# Transmitter.net
KiCad netlist of a schematic drawn in EAGLE
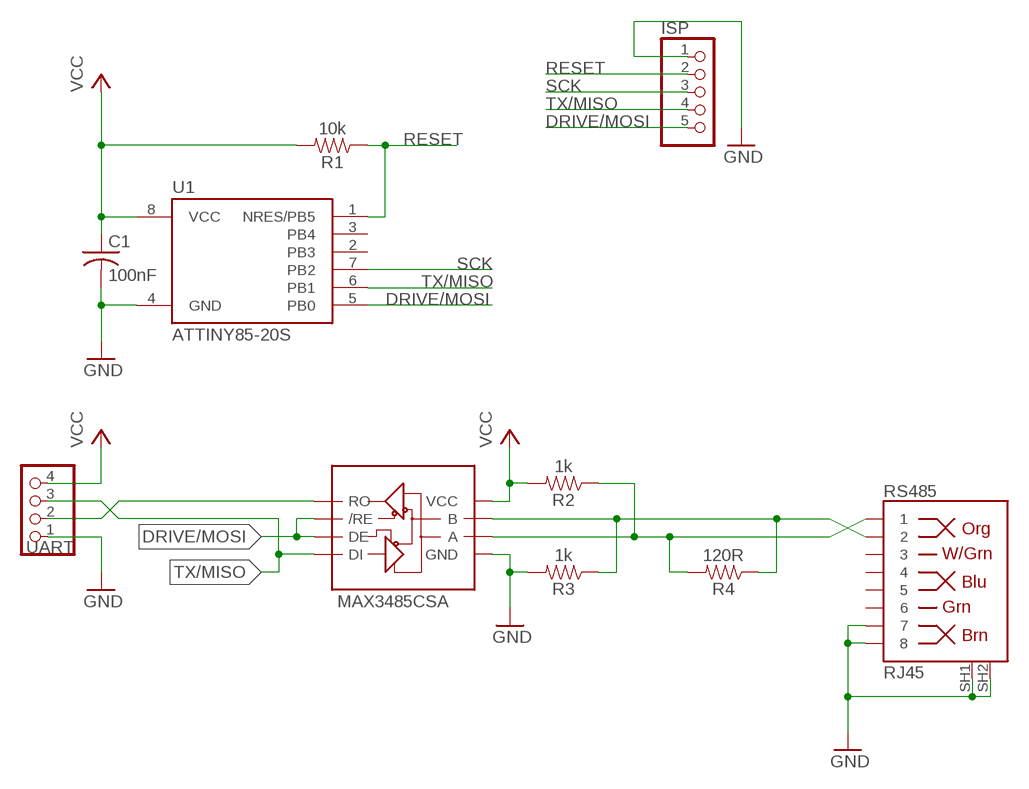
[diagram p0: schematic, sheet 1]

(export (version "E")
  (design (tool "Eeschema 10.0.6"))
  (components
    (comp (ref "C1")
      (value "100nF")
      (footprint "eagle-import:C0603")
      (fields (field (name "MPN") "CC0201KRX5R5BB104"))
      (libsource (lib "eagle-import") (part "C-USC0603"))
    )
    (comp (ref "ISP")
      (value "PINHD-1X5")
      (footprint "eagle-import:1X05")
      (libsource (lib "eagle-import") (part "PINHD-1X5"))
    )
    (comp (ref "R1")
      (value "10k")
      (footprint "eagle-import:0603")
      (libsource (lib "eagle-import") (part "10KOHM-0603-1/10W-1%"))
    )
    (comp (ref "R2")
      (value "1k")
      (footprint "eagle-import:0603")
      (libsource (lib "eagle-import") (part "1KOHM-0603-1/10W-1%"))
    )
    (comp (ref "R3")
      (value "1k")
      (footprint "eagle-import:0603")
      (libsource (lib "eagle-import") (part "1KOHM-0603-1/10W-1%"))
    )
    (comp (ref "R4")
      (value "120R")
      (footprint "eagle-import:0805")
      (libsource (lib "eagle-import") (part "RESISTOR0805"))
    )
    (comp (ref "RS485")
      (value "RJ45")
      (footprint "eagle-import:RJ45-8")
      (libsource (lib "eagle-import") (part "RJ45-8"))
    )
    (comp (ref "U1")
      (value "ATTINY85-20S")
      (footprint "eagle-import:SOIC8_EIAJ_208MIL")
      (libsource (lib "eagle-import") (part "ATTINY85S-20"))
    )
    (comp (ref "U2")
      (value "MAX3485CSA")
      (footprint "eagle-import:SO08")
      (libsource (lib "eagle-import") (part "RS485SOIC"))
    )
    (comp (ref "UART")
      (value "PINHD-1X4")
      (footprint "eagle-import:1X04")
      (libsource (lib "eagle-import") (part "PINHD-1X4"))
    )
  )
  (nets
    (net (code "1") (name "/RESET") (class "Default")
      (node (ref "ISP") (pin "2") (pinfunction "2_2") (pintype "passive"))
      (node (ref "R1") (pin "1") (pinfunction "1_1") (pintype "passive"))
      (node (ref "U1") (pin "1") (pinfunction "NRES/PB5_1") (pintype "bidirectional"))
    )
    (net (code "2") (name "/SCK") (class "Default")
      (node (ref "ISP") (pin "3") (pinfunction "3_3") (pintype "passive"))
      (node (ref "U1") (pin "7") (pinfunction "PB2_7") (pintype "bidirectional"))
    )
    (net (code "3") (name "DRIVE{slash}MOSI") (class "Default")
      (node (ref "ISP") (pin "5") (pinfunction "5_5") (pintype "passive"))
      (node (ref "U1") (pin "5") (pinfunction "PB0_5") (pintype "bidirectional"))
      (node (ref "U2") (pin "2") (pinfunction "/RE_2") (pintype "bidirectional"))
      (node (ref "U2") (pin "3") (pinfunction "DE_3") (pintype "bidirectional"))
    )
    (net (code "4") (name "GND") (class "Default")
      (node (ref "C1") (pin "2") (pinfunction "2_2") (pintype "passive"))
      (node (ref "ISP") (pin "1") (pinfunction "1_1") (pintype "passive"))
      (node (ref "R3") (pin "2") (pinfunction "2_2") (pintype "passive"))
      (node (ref "RS485") (pin "7") (pinfunction "7_7") (pintype "bidirectional"))
      (node (ref "RS485") (pin "8") (pinfunction "8_8") (pintype "bidirectional"))
      (node (ref "RS485") (pin "SH1") (pinfunction "SH1_SH1") (pintype "bidirectional"))
      (node (ref "RS485") (pin "SH2") (pinfunction "SH2_SH2") (pintype "bidirectional"))
      (node (ref "U1") (pin "4") (pinfunction "GND_4") (pintype "power_in"))
      (node (ref "U2") (pin "5") (pinfunction "GND_5") (pintype "bidirectional"))
      (node (ref "UART") (pin "1") (pinfunction "1_1") (pintype "passive"))
    )
    (net (code "5") (name "Net-(U2-A)") (class "Default")
      (node (ref "R2") (pin "1") (pinfunction "1_1") (pintype "passive"))
      (node (ref "R4") (pin "2") (pinfunction "2_2") (pintype "passive"))
      (node (ref "RS485") (pin "1") (pinfunction "1_1") (pintype "bidirectional"))
      (node (ref "U2") (pin "6") (pinfunction "A_6") (pintype "bidirectional"))
    )
    (net (code "6") (name "Net-(U2-B)") (class "Default")
      (node (ref "R3") (pin "1") (pinfunction "1_1") (pintype "passive"))
      (node (ref "R4") (pin "1") (pinfunction "1_1") (pintype "passive"))
      (node (ref "RS485") (pin "2") (pinfunction "2_2") (pintype "bidirectional"))
      (node (ref "U2") (pin "7") (pinfunction "B_7") (pintype "bidirectional"))
    )
    (net (code "7") (name "Net-(U2-RO)") (class "Default")
      (node (ref "U2") (pin "1") (pinfunction "RO_1") (pintype "bidirectional"))
      (node (ref "UART") (pin "2") (pinfunction "2_2") (pintype "passive"))
    )
    (net (code "8") (name "TX{slash}MISO") (class "Default")
      (node (ref "ISP") (pin "4") (pinfunction "4_4") (pintype "passive"))
      (node (ref "U1") (pin "6") (pinfunction "PB1_6") (pintype "bidirectional"))
      (node (ref "U2") (pin "4") (pinfunction "DI_4") (pintype "bidirectional"))
      (node (ref "UART") (pin "3") (pinfunction "3_3") (pintype "passive"))
    )
    (net (code "9") (name "VCC") (class "Default")
      (node (ref "C1") (pin "1") (pinfunction "1_1") (pintype "passive"))
      (node (ref "R1") (pin "2") (pinfunction "2_2") (pintype "passive"))
      (node (ref "R2") (pin "2") (pinfunction "2_2") (pintype "passive"))
      (node (ref "U1") (pin "8") (pinfunction "VCC_8") (pintype "power_in"))
      (node (ref "U2") (pin "8") (pinfunction "VCC_8") (pintype "bidirectional"))
      (node (ref "UART") (pin "4") (pinfunction "4_4") (pintype "passive"))
    )
    (net (code "10") (name "unconnected-(RS485-Pad3)") (class "Default")
      (node (ref "RS485") (pin "3") (pinfunction "3_3") (pintype "bidirectional"))
    )
    (net (code "11") (name "unconnected-(RS485-Pad4)") (class "Default")
      (node (ref "RS485") (pin "4") (pinfunction "4_4") (pintype "bidirectional"))
    )
    (net (code "12") (name "unconnected-(RS485-Pad5)") (class "Default")
      (node (ref "RS485") (pin "5") (pinfunction "5_5") (pintype "bidirectional"))
    )
    (net (code "13") (name "unconnected-(RS485-Pad6)") (class "Default")
      (node (ref "RS485") (pin "6") (pinfunction "6_6") (pintype "bidirectional"))
    )
    (net (code "14") (name "unconnected-(U1-PB3-Pad2)") (class "Default")
      (node (ref "U1") (pin "2") (pinfunction "PB3_2") (pintype "bidirectional"))
    )
    (net (code "15") (name "unconnected-(U1-PB4-Pad3)") (class "Default")
      (node (ref "U1") (pin "3") (pinfunction "PB4_3") (pintype "bidirectional"))
    )
  )
)
